# FEU31_Part2.net
KiCad netlist of a schematic drawn in Altium Designer
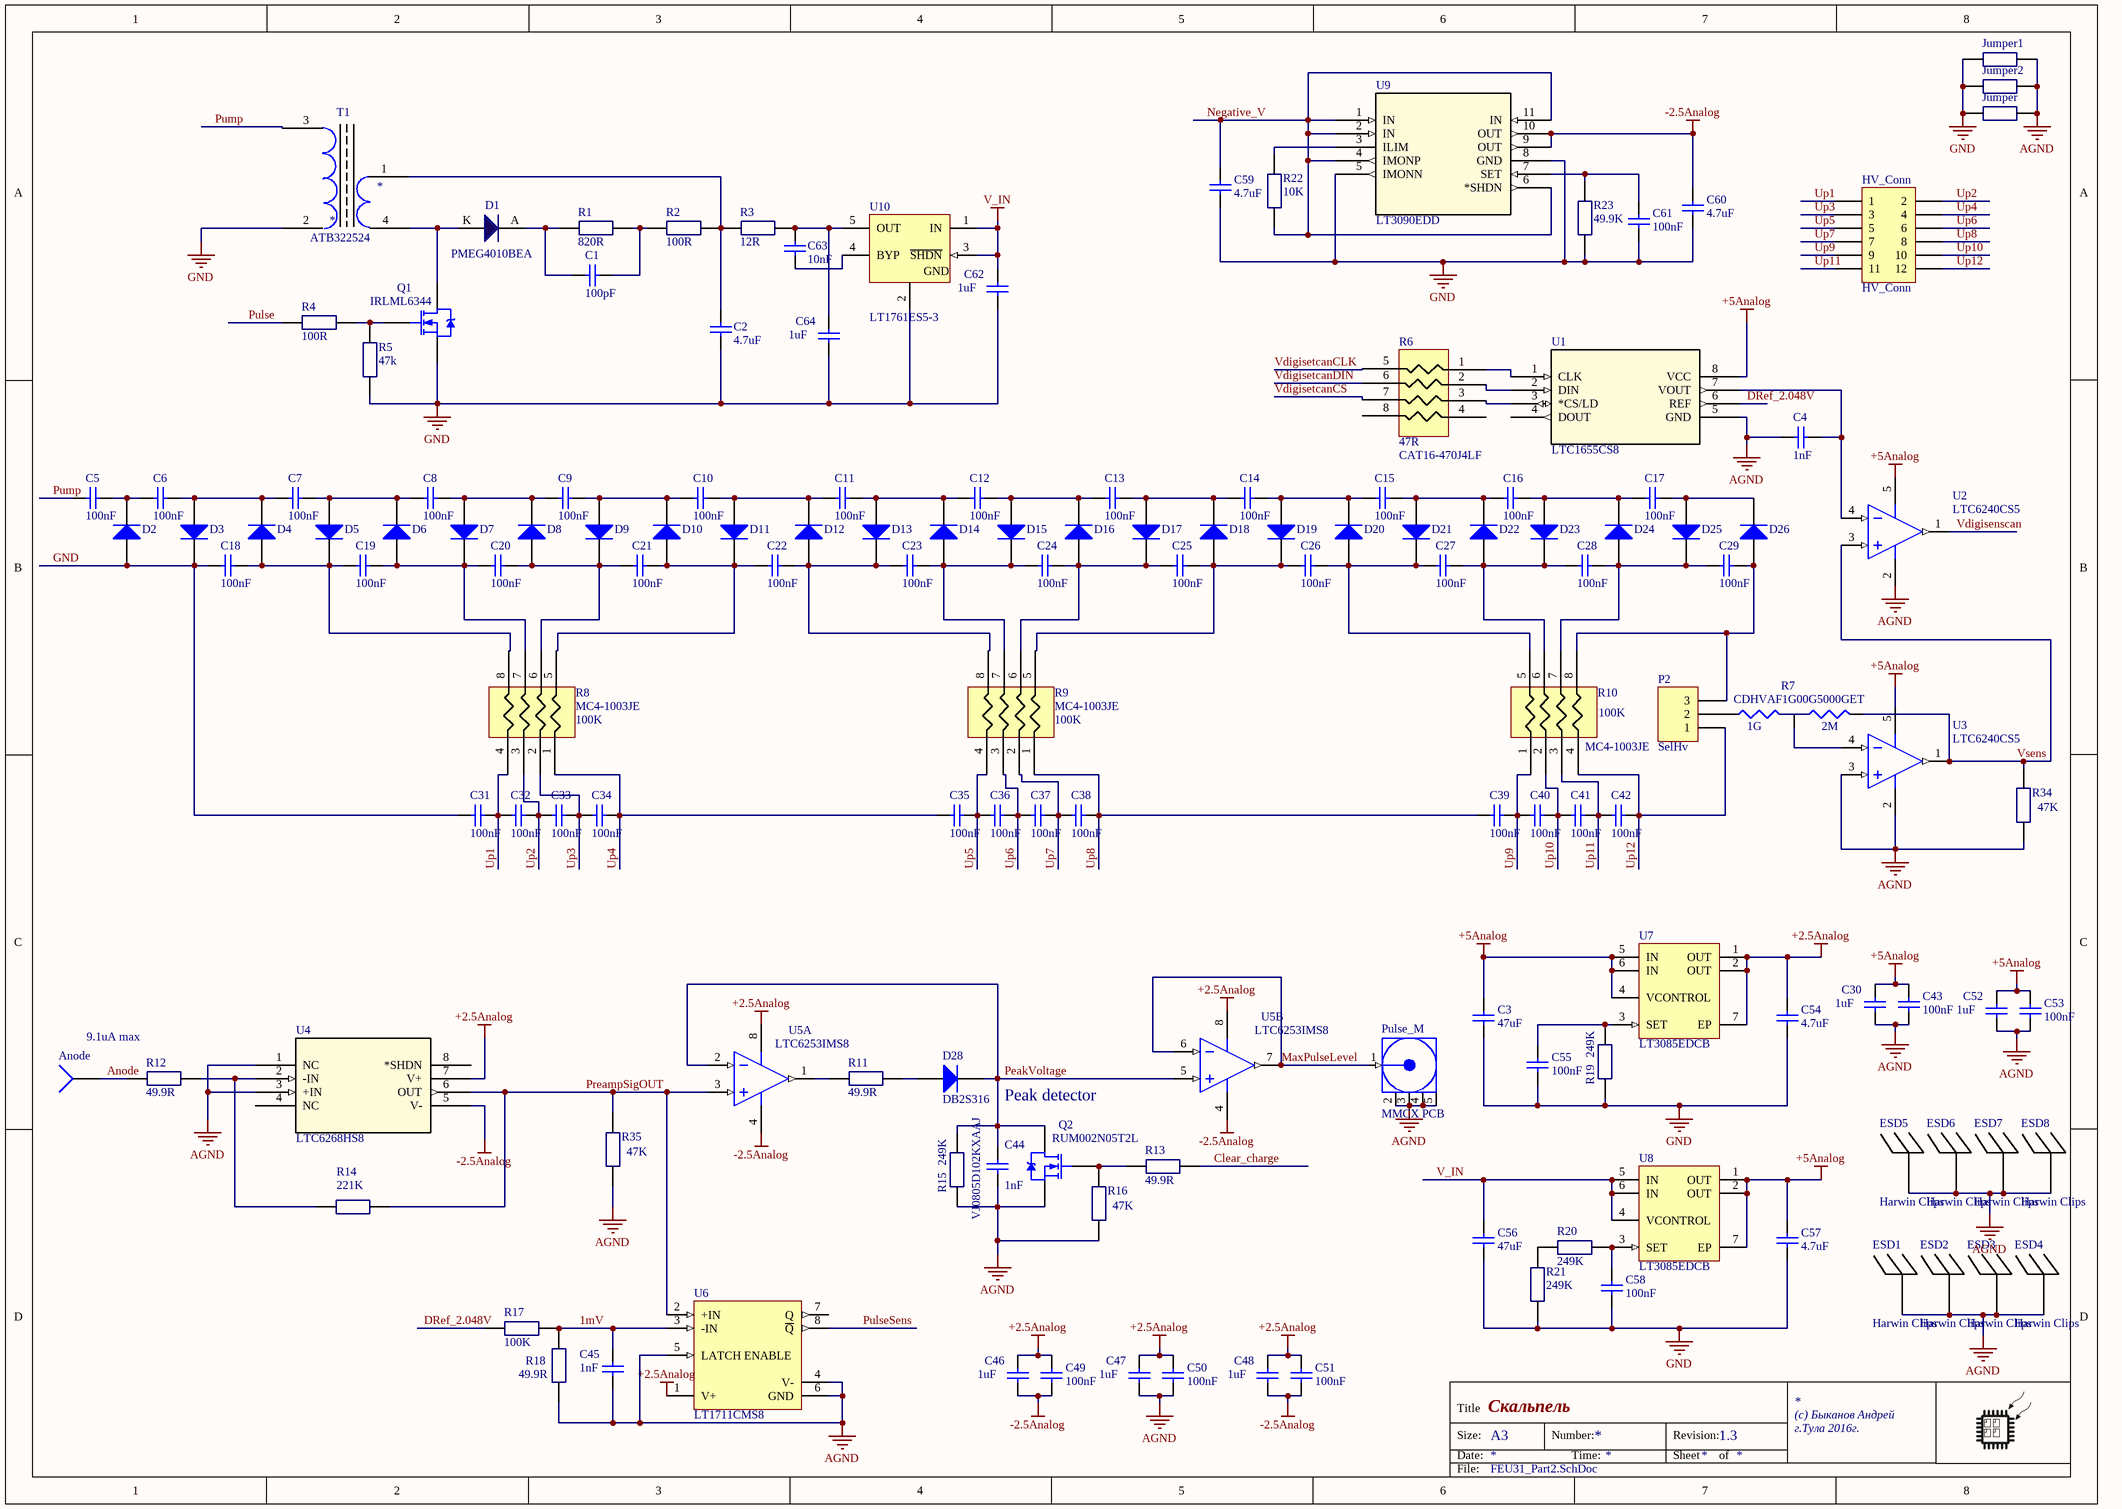
[diagram p0: FEU31_Part2.SchDoc]

(export (version "E")
  (design (tool "Eeschema 10.0.6"))
  (components
    (comp (ref "Anode")
      (value "Anode")
      (footprint "PMTanode")
      (description "Socket")
      (fields (field (name "PUBLISHER") "Altium Limited"))
      (libsource (lib "Miscellaneous Connectors") (part "Socket"))
    )
    (comp (ref "C1")
      (value "100pF")
      (footprint "1608[0603]_CAP")
      (description "Capacitor (Semiconductor SIM Model)")
      (fields (field (name "PUBLISHER") "Altium Limited"))
      (libsource (lib "Miscellaneous Devices") (part "Cap Semi"))
    )
    (comp (ref "C2")
      (value "4.7uF")
      (footprint "Miscellaneous Devices:C1206")
      (description "Capacitor (Semiconductor SIM Model)")
      (fields (field (name "PUBLISHER") "Altium Limited"))
      (libsource (lib "Miscellaneous Devices") (part "Cap Semi"))
    )
    (comp (ref "C3")
      (value "47uF")
      (footprint "C1206")
      (description "Capacitor (Semiconductor SIM Model)")
      (fields (field (name "PUBLISHER") "Altium Limited"))
      (libsource (lib "Miscellaneous Devices") (part "Cap Semi"))
    )
    (comp (ref "C4")
      (value "1nF")
      (footprint "1608[0603]_CAP")
      (description "Capacitor (Semiconductor SIM Model)")
      (fields (field (name "PUBLISHER") "Altium Limited"))
      (libsource (lib "Miscellaneous Devices") (part "Cap Semi"))
    )
    (comp (ref "C5")
      (value "100nF")
      (footprint "Miscellaneous Devices:C1206")
      (description "Capacitor (Semiconductor SIM Model)")
      (fields (field (name "PUBLISHER") "Altium Limited"))
      (libsource (lib "Miscellaneous Devices") (part "Cap Semi"))
    )
    (comp (ref "C6")
      (value "100nF")
      (footprint "Miscellaneous Devices:C1206")
      (description "Capacitor (Semiconductor SIM Model)")
      (fields (field (name "PUBLISHER") "Altium Limited"))
      (libsource (lib "Miscellaneous Devices") (part "Cap Semi"))
    )
    (comp (ref "C7")
      (value "100nF")
      (footprint "Miscellaneous Devices:C1206")
      (description "Capacitor (Semiconductor SIM Model)")
      (fields (field (name "PUBLISHER") "Altium Limited"))
      (libsource (lib "Miscellaneous Devices") (part "Cap Semi"))
    )
    (comp (ref "C8")
      (value "100nF")
      (footprint "Miscellaneous Devices:C1206")
      (description "Capacitor (Semiconductor SIM Model)")
      (fields (field (name "PUBLISHER") "Altium Limited"))
      (libsource (lib "Miscellaneous Devices") (part "Cap Semi"))
    )
    (comp (ref "C9")
      (value "100nF")
      (footprint "Miscellaneous Devices:C1206")
      (description "Capacitor (Semiconductor SIM Model)")
      (fields (field (name "PUBLISHER") "Altium Limited"))
      (libsource (lib "Miscellaneous Devices") (part "Cap Semi"))
    )
    (comp (ref "C10")
      (value "100nF")
      (footprint "Miscellaneous Devices:C1206")
      (description "Capacitor (Semiconductor SIM Model)")
      (fields (field (name "PUBLISHER") "Altium Limited"))
      (libsource (lib "Miscellaneous Devices") (part "Cap Semi"))
    )
    (comp (ref "C11")
      (value "100nF")
      (footprint "Miscellaneous Devices:C1206")
      (description "Capacitor (Semiconductor SIM Model)")
      (fields (field (name "PUBLISHER") "Altium Limited"))
      (libsource (lib "Miscellaneous Devices") (part "Cap Semi"))
    )
    (comp (ref "C12")
      (value "100nF")
      (footprint "Miscellaneous Devices:C1206")
      (description "Capacitor (Semiconductor SIM Model)")
      (fields (field (name "PUBLISHER") "Altium Limited"))
      (libsource (lib "Miscellaneous Devices") (part "Cap Semi"))
    )
    (comp (ref "C13")
      (value "100nF")
      (footprint "Miscellaneous Devices:C1206")
      (description "Capacitor (Semiconductor SIM Model)")
      (fields (field (name "PUBLISHER") "Altium Limited"))
      (libsource (lib "Miscellaneous Devices") (part "Cap Semi"))
    )
    (comp (ref "C14")
      (value "100nF")
      (footprint "Miscellaneous Devices:C1206")
      (description "Capacitor (Semiconductor SIM Model)")
      (fields (field (name "PUBLISHER") "Altium Limited"))
      (libsource (lib "Miscellaneous Devices") (part "Cap Semi"))
    )
    (comp (ref "C15")
      (value "100nF")
      (footprint "Miscellaneous Devices:C1206")
      (description "Capacitor (Semiconductor SIM Model)")
      (fields (field (name "PUBLISHER") "Altium Limited"))
      (libsource (lib "Miscellaneous Devices") (part "Cap Semi"))
    )
    (comp (ref "C16")
      (value "100nF")
      (footprint "Miscellaneous Devices:C1206")
      (description "Capacitor (Semiconductor SIM Model)")
      (fields (field (name "PUBLISHER") "Altium Limited"))
      (libsource (lib "Miscellaneous Devices") (part "Cap Semi"))
    )
    (comp (ref "C17")
      (value "100nF")
      (footprint "Miscellaneous Devices:C1206")
      (description "Capacitor (Semiconductor SIM Model)")
      (fields (field (name "PUBLISHER") "Altium Limited"))
      (libsource (lib "Miscellaneous Devices") (part "Cap Semi"))
    )
    (comp (ref "C18")
      (value "100nF")
      (footprint "Miscellaneous Devices:C1206")
      (description "Capacitor (Semiconductor SIM Model)")
      (fields (field (name "PUBLISHER") "Altium Limited"))
      (libsource (lib "Miscellaneous Devices") (part "Cap Semi"))
    )
    (comp (ref "C19")
      (value "100nF")
      (footprint "Miscellaneous Devices:C1206")
      (description "Capacitor (Semiconductor SIM Model)")
      (fields (field (name "PUBLISHER") "Altium Limited"))
      (libsource (lib "Miscellaneous Devices") (part "Cap Semi"))
    )
    (comp (ref "C20")
      (value "100nF")
      (footprint "Miscellaneous Devices:C1206")
      (description "Capacitor (Semiconductor SIM Model)")
      (fields (field (name "PUBLISHER") "Altium Limited"))
      (libsource (lib "Miscellaneous Devices") (part "Cap Semi"))
    )
    (comp (ref "C21")
      (value "100nF")
      (footprint "Miscellaneous Devices:C1206")
      (description "Capacitor (Semiconductor SIM Model)")
      (fields (field (name "PUBLISHER") "Altium Limited"))
      (libsource (lib "Miscellaneous Devices") (part "Cap Semi"))
    )
    (comp (ref "C22")
      (value "100nF")
      (footprint "Miscellaneous Devices:C1206")
      (description "Capacitor (Semiconductor SIM Model)")
      (fields (field (name "PUBLISHER") "Altium Limited"))
      (libsource (lib "Miscellaneous Devices") (part "Cap Semi"))
    )
    (comp (ref "C23")
      (value "100nF")
      (footprint "Miscellaneous Devices:C1206")
      (description "Capacitor (Semiconductor SIM Model)")
      (fields (field (name "PUBLISHER") "Altium Limited"))
      (libsource (lib "Miscellaneous Devices") (part "Cap Semi"))
    )
    (comp (ref "C24")
      (value "100nF")
      (footprint "Miscellaneous Devices:C1206")
      (description "Capacitor (Semiconductor SIM Model)")
      (fields (field (name "PUBLISHER") "Altium Limited"))
      (libsource (lib "Miscellaneous Devices") (part "Cap Semi"))
    )
    (comp (ref "C25")
      (value "100nF")
      (footprint "Miscellaneous Devices:C1206")
      (description "Capacitor (Semiconductor SIM Model)")
      (fields (field (name "PUBLISHER") "Altium Limited"))
      (libsource (lib "Miscellaneous Devices") (part "Cap Semi"))
    )
    (comp (ref "C26")
      (value "100nF")
      (footprint "Miscellaneous Devices:C1206")
      (description "Capacitor (Semiconductor SIM Model)")
      (fields (field (name "PUBLISHER") "Altium Limited"))
      (libsource (lib "Miscellaneous Devices") (part "Cap Semi"))
    )
    (comp (ref "C27")
      (value "100nF")
      (footprint "Miscellaneous Devices:C1206")
      (description "Capacitor (Semiconductor SIM Model)")
      (fields (field (name "PUBLISHER") "Altium Limited"))
      (libsource (lib "Miscellaneous Devices") (part "Cap Semi"))
    )
    (comp (ref "C28")
      (value "100nF")
      (footprint "Miscellaneous Devices:C1206")
      (description "Capacitor (Semiconductor SIM Model)")
      (fields (field (name "PUBLISHER") "Altium Limited"))
      (libsource (lib "Miscellaneous Devices") (part "Cap Semi"))
    )
    (comp (ref "C29")
      (value "100nF")
      (footprint "Miscellaneous Devices:C1206")
      (description "Capacitor (Semiconductor SIM Model)")
      (fields (field (name "PUBLISHER") "Altium Limited"))
      (libsource (lib "Miscellaneous Devices") (part "Cap Semi"))
    )
    (comp (ref "C30")
      (value "1uF")
      (footprint "1608[0603]_CAP")
      (description "Capacitor (Semiconductor SIM Model)")
      (fields (field (name "PUBLISHER") "Altium Limited"))
      (libsource (lib "Miscellaneous Devices") (part "Cap Semi"))
    )
    (comp (ref "C31")
      (value "100nF")
      (footprint "Miscellaneous Devices:C1206")
      (description "Capacitor (Semiconductor SIM Model)")
      (fields (field (name "PUBLISHER") "Altium Limited"))
      (libsource (lib "Miscellaneous Devices") (part "Cap Semi"))
    )
    (comp (ref "C32")
      (value "100nF")
      (footprint "Miscellaneous Devices:C1206")
      (description "Capacitor (Semiconductor SIM Model)")
      (fields (field (name "PUBLISHER") "Altium Limited"))
      (libsource (lib "Miscellaneous Devices") (part "Cap Semi"))
    )
    (comp (ref "C33")
      (value "100nF")
      (footprint "Miscellaneous Devices:C1206")
      (description "Capacitor (Semiconductor SIM Model)")
      (fields (field (name "PUBLISHER") "Altium Limited"))
      (libsource (lib "Miscellaneous Devices") (part "Cap Semi"))
    )
    (comp (ref "C34")
      (value "100nF")
      (footprint "Miscellaneous Devices:C1206")
      (description "Capacitor (Semiconductor SIM Model)")
      (fields (field (name "PUBLISHER") "Altium Limited"))
      (libsource (lib "Miscellaneous Devices") (part "Cap Semi"))
    )
    (comp (ref "C35")
      (value "100nF")
      (footprint "Miscellaneous Devices:C1206")
      (description "Capacitor (Semiconductor SIM Model)")
      (fields (field (name "PUBLISHER") "Altium Limited"))
      (libsource (lib "Miscellaneous Devices") (part "Cap Semi"))
    )
    (comp (ref "C36")
      (value "100nF")
      (footprint "Miscellaneous Devices:C1206")
      (description "Capacitor (Semiconductor SIM Model)")
      (fields (field (name "PUBLISHER") "Altium Limited"))
      (libsource (lib "Miscellaneous Devices") (part "Cap Semi"))
    )
    (comp (ref "C37")
      (value "100nF")
      (footprint "Miscellaneous Devices:C1206")
      (description "Capacitor (Semiconductor SIM Model)")
      (fields (field (name "PUBLISHER") "Altium Limited"))
      (libsource (lib "Miscellaneous Devices") (part "Cap Semi"))
    )
    (comp (ref "C38")
      (value "100nF")
      (footprint "Miscellaneous Devices:C1206")
      (description "Capacitor (Semiconductor SIM Model)")
      (fields (field (name "PUBLISHER") "Altium Limited"))
      (libsource (lib "Miscellaneous Devices") (part "Cap Semi"))
    )
    (comp (ref "C39")
      (value "100nF")
      (footprint "Miscellaneous Devices:C1206")
      (description "Capacitor (Semiconductor SIM Model)")
      (fields (field (name "PUBLISHER") "Altium Limited"))
      (libsource (lib "Miscellaneous Devices") (part "Cap Semi"))
    )
    (comp (ref "C40")
      (value "100nF")
      (footprint "Miscellaneous Devices:C1206")
      (description "Capacitor (Semiconductor SIM Model)")
      (fields (field (name "PUBLISHER") "Altium Limited"))
      (libsource (lib "Miscellaneous Devices") (part "Cap Semi"))
    )
    (comp (ref "C41")
      (value "100nF")
      (footprint "Miscellaneous Devices:C1206")
      (description "Capacitor (Semiconductor SIM Model)")
      (fields (field (name "PUBLISHER") "Altium Limited"))
      (libsource (lib "Miscellaneous Devices") (part "Cap Semi"))
    )
    (comp (ref "C42")
      (value "100nF")
      (footprint "Miscellaneous Devices:C1206")
      (description "Capacitor (Semiconductor SIM Model)")
      (fields (field (name "PUBLISHER") "Altium Limited"))
      (libsource (lib "Miscellaneous Devices") (part "Cap Semi"))
    )
    (comp (ref "C43")
      (value "100nF")
      (footprint "1608[0603]_CAP")
      (description "Capacitor (Semiconductor SIM Model)")
      (fields (field (name "PUBLISHER") "Altium Limited"))
      (libsource (lib "Miscellaneous Devices") (part "Cap Semi"))
    )
    (comp (ref "C44")
      (value "1nF")
      (footprint "0805_CAP")
      (description "Capacitor (Semiconductor SIM Model)")
      (fields (field (name "ORDER") "VJ0805D102KXAAJ") (field (name "PUBLISHER") "Altium Limited"))
      (libsource (lib "Miscellaneous Devices") (part "Cap Semi"))
    )
    (comp (ref "C45")
      (value "1nF")
      (footprint "1608[0603]_CAP")
      (description "Capacitor (Semiconductor SIM Model)")
      (fields (field (name "PUBLISHER") "Altium Limited"))
      (libsource (lib "Miscellaneous Devices") (part "Cap Semi"))
    )
    (comp (ref "C46")
      (value "1uF")
      (footprint "1608[0603]_CAP")
      (description "Capacitor (Semiconductor SIM Model)")
      (fields (field (name "PUBLISHER") "Altium Limited"))
      (libsource (lib "Miscellaneous Devices") (part "Cap Semi"))
    )
    (comp (ref "C47")
      (value "1uF")
      (footprint "1608[0603]_CAP")
      (description "Capacitor (Semiconductor SIM Model)")
      (fields (field (name "PUBLISHER") "Altium Limited"))
      (libsource (lib "Miscellaneous Devices") (part "Cap Semi"))
    )
    (comp (ref "C48")
      (value "1uF")
      (footprint "1608[0603]_CAP")
      (description "Capacitor (Semiconductor SIM Model)")
      (fields (field (name "PUBLISHER") "Altium Limited"))
      (libsource (lib "Miscellaneous Devices") (part "Cap Semi"))
    )
    (comp (ref "C49")
      (value "100nF")
      (footprint "1608[0603]_CAP")
      (description "Capacitor (Semiconductor SIM Model)")
      (fields (field (name "PUBLISHER") "Altium Limited"))
      (libsource (lib "Miscellaneous Devices") (part "Cap Semi"))
    )
    (comp (ref "C50")
      (value "100nF")
      (footprint "1608[0603]_CAP")
      (description "Capacitor (Semiconductor SIM Model)")
      (fields (field (name "PUBLISHER") "Altium Limited"))
      (libsource (lib "Miscellaneous Devices") (part "Cap Semi"))
    )
    (comp (ref "C51")
      (value "100nF")
      (footprint "1608[0603]_CAP")
      (description "Capacitor (Semiconductor SIM Model)")
      (fields (field (name "PUBLISHER") "Altium Limited"))
      (libsource (lib "Miscellaneous Devices") (part "Cap Semi"))
    )
    (comp (ref "C52")
      (value "1uF")
      (footprint "1608[0603]_CAP")
      (description "Capacitor (Semiconductor SIM Model)")
      (fields (field (name "PUBLISHER") "Altium Limited"))
      (libsource (lib "Miscellaneous Devices") (part "Cap Semi"))
    )
    (comp (ref "C53")
      (value "100nF")
      (footprint "1608[0603]_CAP")
      (description "Capacitor (Semiconductor SIM Model)")
      (fields (field (name "PUBLISHER") "Altium Limited"))
      (libsource (lib "Miscellaneous Devices") (part "Cap Semi"))
    )
    (comp (ref "C54")
      (value "4.7uF")
      (footprint "C1206")
      (description "Capacitor (Semiconductor SIM Model)")
      (fields (field (name "PUBLISHER") "Altium Limited"))
      (libsource (lib "Miscellaneous Devices") (part "Cap Semi"))
    )
    (comp (ref "C55")
      (value "100nF")
      (footprint "1608[0603]_CAP")
      (description "Capacitor (Semiconductor SIM Model)")
      (fields (field (name "PUBLISHER") "Altium Limited"))
      (libsource (lib "Miscellaneous Devices") (part "Cap Semi"))
    )
    (comp (ref "C56")
      (value "47uF")
      (footprint "C1206")
      (description "Capacitor (Semiconductor SIM Model)")
      (fields (field (name "PUBLISHER") "Altium Limited"))
      (libsource (lib "Miscellaneous Devices") (part "Cap Semi"))
    )
    (comp (ref "C57")
      (value "4.7uF")
      (footprint "C1206")
      (description "Capacitor (Semiconductor SIM Model)")
      (fields (field (name "PUBLISHER") "Altium Limited"))
      (libsource (lib "Miscellaneous Devices") (part "Cap Semi"))
    )
    (comp (ref "C58")
      (value "100nF")
      (footprint "1608[0603]_CAP")
      (description "Capacitor (Semiconductor SIM Model)")
      (fields (field (name "PUBLISHER") "Altium Limited"))
      (libsource (lib "Miscellaneous Devices") (part "Cap Semi"))
    )
    (comp (ref "C59")
      (value "4.7uF")
      (footprint "C1206")
      (description "Capacitor (Semiconductor SIM Model)")
      (fields (field (name "PUBLISHER") "Altium Limited"))
      (libsource (lib "Miscellaneous Devices") (part "Cap Semi"))
    )
    (comp (ref "C60")
      (value "4.7uF")
      (footprint "C1206")
      (description "Capacitor (Semiconductor SIM Model)")
      (fields (field (name "PUBLISHER") "Altium Limited"))
      (libsource (lib "Miscellaneous Devices") (part "Cap Semi"))
    )
    (comp (ref "C61")
      (value "100nF")
      (footprint "1608[0603]_CAP")
      (description "Capacitor (Semiconductor SIM Model)")
      (fields (field (name "PUBLISHER") "Altium Limited"))
      (libsource (lib "Miscellaneous Devices") (part "Cap Semi"))
    )
    (comp (ref "C62")
      (value "1uF")
      (footprint "1608[0603]_CAP")
      (description "Capacitor (Semiconductor SIM Model)")
      (fields (field (name "PUBLISHER") "Altium Limited"))
      (libsource (lib "Miscellaneous Devices") (part "Cap Semi"))
    )
    (comp (ref "C63")
      (value "10nF")
      (footprint "1608[0603]_CAP")
      (description "Capacitor (Semiconductor SIM Model)")
      (fields (field (name "PUBLISHER") "Altium Limited"))
      (libsource (lib "Miscellaneous Devices") (part "Cap Semi"))
    )
    (comp (ref "C64")
      (value "1uF")
      (footprint "1608[0603]_CAP")
      (description "Capacitor (Semiconductor SIM Model)")
      (fields (field (name "PUBLISHER") "Altium Limited"))
      (libsource (lib "Miscellaneous Devices") (part "Cap Semi"))
    )
    (comp (ref "D1")
      (value "PMEG4010BEA")
      (footprint "PMEG4010BEA")
      (libsource (lib "My SCH library") (part "PMEG4010BEA"))
    )
    (comp (ref "D2")
      (value "~")
      (footprint "DA2JF8100L")
      (description "Default Diode")
      (fields (field (name "PUBLISHER") "Altium Limited"))
      (libsource (lib "Miscellaneous Devices") (part "Diode"))
    )
    (comp (ref "D3")
      (value "~")
      (footprint "DA2JF8100L")
      (description "Default Diode")
      (fields (field (name "PUBLISHER") "Altium Limited"))
      (libsource (lib "Miscellaneous Devices") (part "Diode"))
    )
    (comp (ref "D4")
      (value "~")
      (footprint "DA2JF8100L")
      (description "Default Diode")
      (fields (field (name "PUBLISHER") "Altium Limited"))
      (libsource (lib "Miscellaneous Devices") (part "Diode"))
    )
    (comp (ref "D5")
      (value "~")
      (footprint "DA2JF8100L")
      (description "Default Diode")
      (fields (field (name "PUBLISHER") "Altium Limited"))
      (libsource (lib "Miscellaneous Devices") (part "Diode"))
    )
    (comp (ref "D6")
      (value "~")
      (footprint "DA2JF8100L")
      (description "Default Diode")
      (fields (field (name "PUBLISHER") "Altium Limited"))
      (libsource (lib "Miscellaneous Devices") (part "Diode"))
    )
    (comp (ref "D7")
      (value "~")
      (footprint "DA2JF8100L")
      (description "Default Diode")
      (fields (field (name "PUBLISHER") "Altium Limited"))
      (libsource (lib "Miscellaneous Devices") (part "Diode"))
    )
    (comp (ref "D8")
      (value "~")
      (footprint "DA2JF8100L")
      (description "Default Diode")
      (fields (field (name "PUBLISHER") "Altium Limited"))
      (libsource (lib "Miscellaneous Devices") (part "Diode"))
    )
    (comp (ref "D9")
      (value "~")
      (footprint "DA2JF8100L")
      (description "Default Diode")
      (fields (field (name "PUBLISHER") "Altium Limited"))
      (libsource (lib "Miscellaneous Devices") (part "Diode"))
    )
    (comp (ref "D10")
      (value "~")
      (footprint "DA2JF8100L")
      (description "Default Diode")
      (fields (field (name "PUBLISHER") "Altium Limited"))
      (libsource (lib "Miscellaneous Devices") (part "Diode"))
    )
    (comp (ref "D11")
      (value "~")
      (footprint "DA2JF8100L")
      (description "Default Diode")
      (fields (field (name "PUBLISHER") "Altium Limited"))
      (libsource (lib "Miscellaneous Devices") (part "Diode"))
    )
    (comp (ref "D12")
      (value "~")
      (footprint "DA2JF8100L")
      (description "Default Diode")
      (fields (field (name "PUBLISHER") "Altium Limited"))
      (libsource (lib "Miscellaneous Devices") (part "Diode"))
    )
    (comp (ref "D13")
      (value "~")
      (footprint "DA2JF8100L")
      (description "Default Diode")
      (fields (field (name "PUBLISHER") "Altium Limited"))
      (libsource (lib "Miscellaneous Devices") (part "Diode"))
    )
    (comp (ref "D14")
      (value "~")
      (footprint "DA2JF8100L")
      (description "Default Diode")
      (fields (field (name "PUBLISHER") "Altium Limited"))
      (libsource (lib "Miscellaneous Devices") (part "Diode"))
    )
    (comp (ref "D15")
      (value "~")
      (footprint "DA2JF8100L")
      (description "Default Diode")
      (fields (field (name "PUBLISHER") "Altium Limited"))
      (libsource (lib "Miscellaneous Devices") (part "Diode"))
    )
    (comp (ref "D16")
      (value "~")
      (footprint "DA2JF8100L")
      (description "Default Diode")
      (fields (field (name "PUBLISHER") "Altium Limited"))
      (libsource (lib "Miscellaneous Devices") (part "Diode"))
    )
    (comp (ref "D17")
      (value "~")
      (footprint "DA2JF8100L")
      (description "Default Diode")
      (fields (field (name "PUBLISHER") "Altium Limited"))
      (libsource (lib "Miscellaneous Devices") (part "Diode"))
    )
    (comp (ref "D18")
      (value "~")
      (footprint "DA2JF8100L")
      (description "Default Diode")
      (fields (field (name "PUBLISHER") "Altium Limited"))
      (libsource (lib "Miscellaneous Devices") (part "Diode"))
    )
    (comp (ref "D19")
      (value "~")
      (footprint "DA2JF8100L")
      (description "Default Diode")
      (fields (field (name "PUBLISHER") "Altium Limited"))
      (libsource (lib "Miscellaneous Devices") (part "Diode"))
    )
    (comp (ref "D20")
      (value "~")
      (footprint "DA2JF8100L")
      (description "Default Diode")
      (fields (field (name "PUBLISHER") "Altium Limited"))
      (libsource (lib "Miscellaneous Devices") (part "Diode"))
    )
    (comp (ref "D21")
      (value "~")
      (footprint "DA2JF8100L")
      (description "Default Diode")
      (fields (field (name "PUBLISHER") "Altium Limited"))
      (libsource (lib "Miscellaneous Devices") (part "Diode"))
    )
    (comp (ref "D22")
      (value "~")
      (footprint "DA2JF8100L")
      (description "Default Diode")
      (fields (field (name "PUBLISHER") "Altium Limited"))
      (libsource (lib "Miscellaneous Devices") (part "Diode"))
    )
    (comp (ref "D23")
      (value "~")
      (footprint "DA2JF8100L")
      (description "Default Diode")
      (fields (field (name "PUBLISHER") "Altium Limited"))
      (libsource (lib "Miscellaneous Devices") (part "Diode"))
    )
    (comp (ref "D24")
      (value "~")
      (footprint "DA2JF8100L")
      (description "Default Diode")
      (fields (field (name "PUBLISHER") "Altium Limited"))
      (libsource (lib "Miscellaneous Devices") (part "Diode"))
    )
    (comp (ref "D25")
      (value "~")
      (footprint "DA2JF8100L")
      (description "Default Diode")
      (fields (field (name "PUBLISHER") "Altium Limited"))
      (libsource (lib "Miscellaneous Devices") (part "Diode"))
    )
    (comp (ref "D26")
      (value "~")
      (footprint "DA2JF8100L")
      (description "Default Diode")
      (fields (field (name "PUBLISHER") "Altium Limited"))
      (libsource (lib "Miscellaneous Devices") (part "Diode"))
    )
    (comp (ref "D28")
      (value "DB2S316")
      (footprint "SSMini2-F5-B")
      (description "Default Diode")
      (fields (field (name "PUBLISHER") "Altium Limited"))
      (libsource (lib "Miscellaneous Devices") (part "Diode"))
    )
    (comp (ref "ESD1")
      (value "Harwin Clips")
      (footprint "HARWIN - S0981-46R - CLIP")
      (libsource (lib "My SCH library") (part "Harwin Clips"))
    )
    (comp (ref "ESD2")
      (value "Harwin Clips")
      (footprint "HARWIN - S0981-46R - CLIP")
      (libsource (lib "My SCH library") (part "Harwin Clips"))
    )
    (comp (ref "ESD3")
      (value "Harwin Clips")
      (footprint "HARWIN - S0981-46R - CLIP")
      (libsource (lib "My SCH library") (part "Harwin Clips"))
    )
    (comp (ref "ESD4")
      (value "Harwin Clips")
      (footprint "HARWIN - S0981-46R - CLIP")
      (libsource (lib "My SCH library") (part "Harwin Clips"))
    )
    (comp (ref "ESD5")
      (value "Harwin Clips")
      (footprint "HARWIN - S0981-46R - CLIP")
      (libsource (lib "My SCH library") (part "Harwin Clips"))
    )
    (comp (ref "ESD6")
      (value "Harwin Clips")
      (footprint "HARWIN - S0981-46R - CLIP")
      (libsource (lib "My SCH library") (part "Harwin Clips"))
    )
    (comp (ref "ESD7")
      (value "Harwin Clips")
      (footprint "HARWIN - S0981-46R - CLIP")
      (libsource (lib "My SCH library") (part "Harwin Clips"))
    )
    (comp (ref "ESD8")
      (value "Harwin Clips")
      (footprint "HARWIN - S0981-46R - CLIP")
      (libsource (lib "My SCH library") (part "Harwin Clips"))
    )
    (comp (ref "HV_Conn")
      (value "HV_Conn")
      (footprint "HDR2X6H")
      (description "Header, 6-Pin, Dual row, Right Angle")
      (fields (field (name "PUBLISHER") "Altium Limited"))
      (libsource (lib "Miscellaneous Connectors") (part "Header 6X2H"))
    )
    (comp (ref "Jumper")
      (value "~")
      (footprint "0402 jumper")
      (libsource (lib "Микрон-3") (part "Resistor 0805"))
    )
    (comp (ref "Jumper1")
      (value "~")
      (footprint "0402 jumper")
      (libsource (lib "Микрон-3") (part "Resistor 0805"))
    )
    (comp (ref "Jumper2")
      (value "~")
      (footprint "0402 jumper")
      (libsource (lib "Микрон-3") (part "Resistor 0805"))
    )
    (comp (ref "P2")
      (value "SelHv")
      (footprint "HDR1X3")
      (description "Header, 3-Pin")
      (fields (field (name "PUBLISHER") "Altium Limited"))
      (libsource (lib "Miscellaneous Connectors") (part "Header 3"))
    )
    (comp (ref "Pulse_M")
      (value "MMCX PCB")
      (footprint "MMCX2.54-V5")
      (description "RF Coaxial PCB Connector, MMCX; Thru-Hole, Vertical Mount Plug,  50 Ohm Impedance")
      (fields (field (name "PUBLISHER") "Altium Limited"))
      (libsource (lib "Miscellaneous Connectors") (part "COAX-M"))
    )
    (comp (ref "Q1")
      (value "IRLML6344")
      (footprint "SOT-23_N")
      (description "HEXFET Power MOSFET")
      (fields (field (name "PUBLISHER") "Altium Limited"))
      (libsource (lib "IR Discrete MOSFET - Power") (part "IRLML2402"))
    )
    (comp (ref "Q2")
      (value "RUM002N05T2L")
      (footprint "RUM002N05")
      (description "HEXFET Power MOSFET")
      (fields (field (name "PUBLISHER") "Altium Limited"))
      (libsource (lib "IR Discrete MOSFET - Power") (part "IRLML2402"))
    )
    (comp (ref "R1")
      (value "820R")
      (footprint "1608[0603]_RES")
      (libsource (lib "Микрон-3") (part "Resistor 0805"))
    )
    (comp (ref "R2")
      (value "100R")
      (footprint "1608[0603]_RES")
      (libsource (lib "Микрон-3") (part "Resistor 0805"))
    )
    (comp (ref "R3")
      (value "12R")
      (footprint "1608[0603]_RES")
      (libsource (lib "Микрон-3") (part "Resistor 0805"))
    )
    (comp (ref "R4")
      (value "100R")
      (footprint "1608[0603]_RES")
      (libsource (lib "Микрон-3") (part "Resistor 0805"))
    )
    (comp (ref "R5")
      (value "47k")
      (footprint "1608[0603]_RES")
      (libsource (lib "Микрон-3") (part "Resistor 0805"))
    )
    (comp (ref "R6")
      (value "47R")
      (footprint "CAT16-470J4LF")
      (fields (field (name "ORDER") "CAT16-470J4LF"))
      (libsource (lib "") (part "CAT16-470J4LF_2"))
    )
    (comp (ref "R7")
      (value "1G")
      (footprint "CDHV2512")
      (fields
        (field (name "VALUE2") "2M")
        (field (name "ORDER") "CDHVAF1G00G5000GET")
        (field (name "Comment") "CDHVAF1G00G5000GET")
        (field (name "PUBLISHER") "Altium Limited")
      )
      (libsource (lib "My SCH library") (part "CDHVAF1G00G5000GET"))
    )
    (comp (ref "R8")
      (value "MC4-1003JE")
      (footprint "MC4")
      (fields (field (name "ALTIUM_VALUE") "100K"))
      (libsource (lib "") (part "CAT16-470J4LF_1"))
    )
    (comp (ref "R9")
      (value "MC4-1003JE")
      (footprint "MC4")
      (fields (field (name "ALTIUM_VALUE") "100K"))
      (libsource (lib "") (part "CAT16-470J4LF_1"))
    )
    (comp (ref "R10")
      (value "MC4-1003JE")
      (footprint "MC4")
      (fields (field (name "ALTIUM_VALUE") "100K"))
      (libsource (lib "My SCH library") (part "CAT16-470J4LF"))
    )
    (comp (ref "R11")
      (value "49.9R")
      (footprint "1608[0603]_RES")
      (libsource (lib "Микрон-3") (part "Resistor 0805"))
    )
    (comp (ref "R12")
      (value "49.9R")
      (footprint "1608[0603]_RES")
      (libsource (lib "Микрон-3") (part "Resistor 0805"))
    )
    (comp (ref "R13")
      (value "49.9R")
      (footprint "1608[0603]_RES")
      (libsource (lib "Микрон-3") (part "Resistor 0805"))
    )
    (comp (ref "R14")
      (value "221K")
      (footprint "1608[0603]_RES")
      (libsource (lib "Микрон-3") (part "Resistor 0805"))
    )
    (comp (ref "R15")
      (value "249K")
      (footprint "1608[0603]_RES")
      (libsource (lib "Микрон-3") (part "Resistor 0805"))
    )
    (comp (ref "R16")
      (value "47K")
      (footprint "1608[0603]_RES")
      (libsource (lib "Микрон-3") (part "Resistor 0805"))
    )
    (comp (ref "R17")
      (value "100K")
      (footprint "1608[0603]_RES")
      (libsource (lib "Микрон-3") (part "Resistor 0805"))
    )
    (comp (ref "R18")
      (value "49.9R")
      (footprint "1608[0603]_RES")
      (libsource (lib "Микрон-3") (part "Resistor 0805"))
    )
    (comp (ref "R19")
      (value "249K")
      (footprint "1608[0603]_RES")
      (libsource (lib "Микрон-3") (part "Resistor 0805"))
    )
    (comp (ref "R20")
      (value "249K")
      (footprint "1608[0603]_RES")
      (libsource (lib "Микрон-3") (part "Resistor 0805"))
    )
    (comp (ref "R21")
      (value "249K")
      (footprint "1608[0603]_RES")
      (libsource (lib "Микрон-3") (part "Resistor 0805"))
    )
    (comp (ref "R22")
      (value "10K")
      (footprint "1608[0603]_RES")
      (libsource (lib "Микрон-3") (part "Resistor 0805"))
    )
    (comp (ref "R23")
      (value "49.9K")
      (footprint "1608[0603]_RES")
      (libsource (lib "Микрон-3") (part "Resistor 0805"))
    )
    (comp (ref "R34")
      (value "47K")
      (footprint "1608[0603]_RES")
      (libsource (lib "Микрон-3") (part "Resistor 0805"))
    )
    (comp (ref "R35")
      (value "47K")
      (footprint "1608[0603]_RES")
      (libsource (lib "Микрон-3") (part "Resistor 0805"))
    )
    (comp (ref "T1")
      (value "ATB322524")
      (footprint "ATB322515-0110")
      (libsource (lib "My SCH library") (part "ATB322515-0110"))
    )
    (comp (ref "U1")
      (value "LTC1655CS8")
      (footprint "SO-8_S")
      (description "Imported")
      (fields (field (name "MANUFACTURER_PART_NUMBER") "ltc1655cs8"))
      (libsource (lib "2017-08-04_11-27-58") (part "LTC1655CS8"))
    )
    (comp (ref "U2")
      (value "LTC6240CS5")
      (footprint "LT-S5-5-TSOT-23_N")
      (fields
        (field (name "LINEAR TECHNOLOGY PART NUMBER") "LTC6240")
        (field (name "MANUFACTURER") "Linear Technology")
        (field (name "PARTNUMBER") "LTC6240CS5#PBF")
      )
      (libsource (lib "Linear Technology Operational Amplifiers (LT2000-LT6000)") (part "LTC6240CS5#PBF"))
    )
    (comp (ref "U3")
      (value "LTC6240CS5")
      (footprint "LT-S5-5-TSOT-23_N")
      (fields
        (field (name "LINEAR TECHNOLOGY PART NUMBER") "LTC6240")
        (field (name "MANUFACTURER") "Linear Technology")
        (field (name "PARTNUMBER") "LTC6240CS5#PBF")
      )
      (libsource (lib "Linear Technology Operational Amplifiers (LT2000-LT6000)") (part "LTC6240CS5#PBF"))
    )
    (comp (ref "U4")
      (value "LTC6268HS8")
      (footprint "SO-8_S")
      (description "Imported")
      (fields (field (name "MANUFACTURER_PART_NUMBER") "ltc6268hs8#pbf"))
      (libsource (lib "2017-08-04_13-53-15") (part "LTC6268HS8PBF"))
    )
    (comp (ref "U5")
      (value "LTC6253IMS8")
      (footprint "LT-MS8-8_N")
      (fields
        (field (name "LINEAR TECHNOLOGY PART NUMBER") "LTC6253")
        (field (name "MANUFACTURER") "Linear Technology")
        (field (name "PARTNUMBER") "LTC6253IMS8#PBF")
      )
      (libsource (lib "Linear Technology Operational Amplifiers (LT2000-LT6000)") (part "LTC6253IMS8#PBF"))
    )
    (comp (ref "U6")
      (value "LT1711CMS8")
      (footprint "LT-MS8_N")
      (fields (field (name "GENERIC PART NUMBER") "LT1711") (field (name "MANUFACTURER") "Linear Technology"))
      (libsource (lib "Linear Technology Comparators") (part "LT1711CMS8"))
    )
    (comp (ref "U7")
      (value "LT3085EDCB")
      (footprint "LT-DCB-6_V")
      (fields (field (name "MANUFACTURER") "Linear Technology") (field (name "PARTNUMBER") "LT3085EDCB#PBF"))
      (libsource (lib "Linear Technology Power Management Current Sources") (part "LT3085EDCB#PBF"))
    )
    (comp (ref "U8")
      (value "LT3085EDCB")
      (footprint "LT-DCB-6_V")
      (fields (field (name "MANUFACTURER") "Linear Technology") (field (name "PARTNUMBER") "LT3085EDCB#PBF"))
      (libsource (lib "Linear Technology Power Management Current Sources") (part "LT3085EDCB#PBF"))
    )
    (comp (ref "U9")
      (value "LT3090EDD")
      (footprint "DFN-10_DD")
      (description "Imported")
      (fields (field (name "MANUFACTURER_PART_NUMBER") "lt3090edd#pbf"))
      (libsource (lib "2017-08-07_08-21-16") (part "LT3090EDDPBF"))
    )
    (comp (ref "U10")
      (value "LT1761ES5-3")
      (footprint "LT-S5-5-TSOT-23_N")
      (fields (field (name "MANUFACTURER") "Linear Technology"))
      (libsource (lib "Linear Technology Power Management LDO Linear Regulators") (part "LT1761ES5-3"))
    )
  )
  (nets
    (net (code "1") (name "+2.5Analog") (class "Default")
      (node (ref "C46") (pin "1") (pinfunction "1_1") (pintype "passive"))
      (node (ref "C47") (pin "1") (pinfunction "1_1") (pintype "passive"))
      (node (ref "C48") (pin "1") (pinfunction "1_1") (pintype "passive"))
      (node (ref "C49") (pin "1") (pinfunction "1_1") (pintype "passive"))
      (node (ref "C50") (pin "1") (pinfunction "1_1") (pintype "passive"))
      (node (ref "C51") (pin "1") (pinfunction "1_1") (pintype "passive"))
      (node (ref "C54") (pin "1") (pinfunction "1_1") (pintype "passive"))
      (node (ref "U4") (pin "7") (pinfunction "V+_7") (pintype "power_in"))
      (node (ref "U5") (pin "8") (pinfunction "V+_8") (pintype "power_in"))
      (node (ref "U6") (pin "1") (pinfunction "V+_1") (pintype "power_in"))
      (node (ref "U7") (pin "1") (pinfunction "OUT_1") (pintype "power_in"))
      (node (ref "U7") (pin "2") (pinfunction "OUT_2") (pintype "power_in"))
      (node (ref "U7") (pin "7") (pinfunction "EP_7") (pintype "power_in"))
    )
    (net (code "2") (name "+5Analog") (class "Default")
      (node (ref "C3") (pin "1") (pinfunction "1_1") (pintype "passive"))
      (node (ref "C30") (pin "1") (pinfunction "1_1") (pintype "passive"))
      (node (ref "C43") (pin "1") (pinfunction "1_1") (pintype "passive"))
      (node (ref "C52") (pin "1") (pinfunction "1_1") (pintype "passive"))
      (node (ref "C53") (pin "1") (pinfunction "1_1") (pintype "passive"))
      (node (ref "C57") (pin "1") (pinfunction "1_1") (pintype "passive"))
      (node (ref "U1") (pin "8") (pinfunction "VCC_8") (pintype "power_in"))
      (node (ref "U2") (pin "5") (pinfunction "V+_5") (pintype "power_in"))
      (node (ref "U3") (pin "5") (pinfunction "V+_5") (pintype "power_in"))
      (node (ref "U7") (pin "4") (pinfunction "VCONTROL_4") (pintype "power_in"))
      (node (ref "U7") (pin "5") (pinfunction "IN_5") (pintype "power_in"))
      (node (ref "U7") (pin "6") (pinfunction "IN_6") (pintype "power_in"))
      (node (ref "U8") (pin "1") (pinfunction "OUT_1") (pintype "power_in"))
      (node (ref "U8") (pin "2") (pinfunction "OUT_2") (pintype "power_in"))
      (node (ref "U8") (pin "7") (pinfunction "EP_7") (pintype "power_in"))
    )
    (net (code "3") (name "-2.5Analog") (class "Default")
      (node (ref "C46") (pin "2") (pinfunction "2_2") (pintype "passive"))
      (node (ref "C48") (pin "2") (pinfunction "2_2") (pintype "passive"))
      (node (ref "C49") (pin "2") (pinfunction "2_2") (pintype "passive"))
      (node (ref "C51") (pin "2") (pinfunction "2_2") (pintype "passive"))
      (node (ref "C60") (pin "1") (pinfunction "1_1") (pintype "passive"))
      (node (ref "U4") (pin "5") (pinfunction "V-_5") (pintype "power_in"))
      (node (ref "U5") (pin "4") (pinfunction "V-_4") (pintype "power_in"))
      (node (ref "U9") (pin "10") (pinfunction "OUT_10") (pintype "output"))
      (node (ref "U9") (pin "9") (pinfunction "OUT_9") (pintype "output"))
    )
    (net (code "4") (name "/1mV") (class "Default")
      (node (ref "C45") (pin "1") (pinfunction "1_1") (pintype "passive"))
      (node (ref "R17") (pin "2") (pinfunction "2_2") (pintype "passive"))
      (node (ref "R18") (pin "1") (pinfunction "A_1") (pintype "passive"))
      (node (ref "U6") (pin "3") (pinfunction "-IN_3") (pintype "input"))
    )
    (net (code "5") (name "/Anode") (class "Default")
      (node (ref "Anode") (pin "1") (pinfunction "1_1") (pintype "passive"))
      (node (ref "R12") (pin "1") (pinfunction "A_1") (pintype "passive"))
    )
    (net (code "6") (name "/Clear_charge") (class "Default")
      (node (ref "R13") (pin "2") (pinfunction "2_2") (pintype "passive"))
    )
    (net (code "7") (name "/DRef_2.048V") (class "Default")
      (node (ref "R17") (pin "1") (pinfunction "A_1") (pintype "passive"))
      (node (ref "U1") (pin "6") (pinfunction "REF_6") (pintype "output"))
    )
    (net (code "8") (name "/MaxPulseLevel") (class "Default")
      (node (ref "Pulse_M") (pin "1") (pinfunction "Signal_1") (pintype "input"))
      (node (ref "U5") (pin "6") (pinfunction "-IN_B_6") (pintype "input"))
      (node (ref "U5") (pin "7") (pinfunction "OUT_B_7") (pintype "output"))
    )
    (net (code "9") (name "/Negative_V") (class "Default")
      (node (ref "C59") (pin "1") (pinfunction "1_1") (pintype "passive"))
      (node (ref "R22") (pin "1") (pinfunction "A_1") (pintype "passive"))
      (node (ref "U9") (pin "1") (pinfunction "IN_1") (pintype "input"))
      (node (ref "U9") (pin "11") (pinfunction "IN_11") (pintype "input"))
      (node (ref "U9") (pin "2") (pinfunction "IN_2") (pintype "input"))
      (node (ref "U9") (pin "4") (pinfunction "IMONP_4") (pintype "output"))
      (node (ref "U9") (pin "6") (pinfunction "*SHDN_6") (pintype "output"))
    )
    (net (code "10") (name "/PeakVoltage") (class "Default")
      (node (ref "C44") (pin "1") (pinfunction "1_1") (pintype "passive"))
      (node (ref "D28") (pin "2") (pinfunction "K_2") (pintype "passive"))
      (node (ref "Q2") (pin "3") (pinfunction "D_3") (pintype "passive"))
      (node (ref "R15") (pin "1") (pinfunction "A_1") (pintype "passive"))
      (node (ref "U5") (pin "2") (pinfunction "-IN_A_2") (pintype "input"))
      (node (ref "U5") (pin "5") (pinfunction "+IN_B_5") (pintype "input"))
    )
    (net (code "11") (name "/PreampSigOUT") (class "Default")
      (node (ref "R14") (pin "1") (pinfunction "A_1") (pintype "passive"))
      (node (ref "R35") (pin "1") (pinfunction "A_1") (pintype "passive"))
      (node (ref "U4") (pin "6") (pinfunction "OUT_6") (pintype "output"))
      (node (ref "U5") (pin "3") (pinfunction "+IN_A_3") (pintype "input"))
      (node (ref "U6") (pin "2") (pinfunction "+IN_2") (pintype "input"))
    )
    (net (code "12") (name "/Pulse") (class "Default")
      (node (ref "R4") (pin "1") (pinfunction "A_1") (pintype "passive"))
    )
    (net (code "13") (name "/PulseSens") (class "Default")
      (node (ref "U6") (pin "8") (pinfunction "~{Q}_8") (pintype "output"))
    )
    (net (code "14") (name "/Pump") (class "Default")
      (node (ref "C5") (pin "2") (pinfunction "2_2") (pintype "passive"))
      (node (ref "T1") (pin "3") (pinfunction "3_3") (pintype "passive"))
    )
    (net (code "15") (name "/Up1") (class "Default")
      (node (ref "C31") (pin "1") (pinfunction "1_1") (pintype "passive"))
      (node (ref "C32") (pin "2") (pinfunction "2_2") (pintype "passive"))
      (node (ref "HV_Conn") (pin "1") (pinfunction "1_1") (pintype "passive"))
      (node (ref "R8") (pin "4") (pinfunction "4_4") (pintype "passive"))
    )
    (net (code "16") (name "/Up2") (class "Default")
      (node (ref "C32") (pin "1") (pinfunction "1_1") (pintype "passive"))
      (node (ref "C33") (pin "2") (pinfunction "2_2") (pintype "passive"))
      (node (ref "HV_Conn") (pin "2") (pinfunction "2_2") (pintype "passive"))
      (node (ref "R8") (pin "3") (pinfunction "3_3") (pintype "passive"))
    )
    (net (code "17") (name "/Up3") (class "Default")
      (node (ref "C33") (pin "1") (pinfunction "1_1") (pintype "passive"))
      (node (ref "C34") (pin "2") (pinfunction "2_2") (pintype "passive"))
      (node (ref "HV_Conn") (pin "3") (pinfunction "3_3") (pintype "passive"))
      (node (ref "R8") (pin "2") (pinfunction "2_2") (pintype "passive"))
    )
    (net (code "18") (name "/Up4") (class "Default")
      (node (ref "C34") (pin "1") (pinfunction "1_1") (pintype "passive"))
      (node (ref "C35") (pin "2") (pinfunction "2_2") (pintype "passive"))
      (node (ref "HV_Conn") (pin "4") (pinfunction "4_4") (pintype "passive"))
      (node (ref "R8") (pin "1") (pinfunction "1_1") (pintype "passive"))
    )
    (net (code "19") (name "/Up5") (class "Default")
      (node (ref "C35") (pin "1") (pinfunction "1_1") (pintype "passive"))
      (node (ref "C36") (pin "2") (pinfunction "2_2") (pintype "passive"))
      (node (ref "HV_Conn") (pin "5") (pinfunction "5_5") (pintype "passive"))
      (node (ref "R9") (pin "4") (pinfunction "4_4") (pintype "passive"))
    )
    (net (code "20") (name "/Up6") (class "Default")
      (node (ref "C36") (pin "1") (pinfunction "1_1") (pintype "passive"))
      (node (ref "C37") (pin "2") (pinfunction "2_2") (pintype "passive"))
      (node (ref "HV_Conn") (pin "6") (pinfunction "6_6") (pintype "passive"))
      (node (ref "R9") (pin "3") (pinfunction "3_3") (pintype "passive"))
    )
    (net (code "21") (name "/Up7") (class "Default")
      (node (ref "C37") (pin "1") (pinfunction "1_1") (pintype "passive"))
      (node (ref "C38") (pin "2") (pinfunction "2_2") (pintype "passive"))
      (node (ref "HV_Conn") (pin "7") (pinfunction "7_7") (pintype "passive"))
      (node (ref "R9") (pin "2") (pinfunction "2_2") (pintype "passive"))
    )
    (net (code "22") (name "/Up8") (class "Default")
      (node (ref "C38") (pin "1") (pinfunction "1_1") (pintype "passive"))
      (node (ref "C39") (pin "2") (pinfunction "2_2") (pintype "passive"))
      (node (ref "HV_Conn") (pin "8") (pinfunction "8_8") (pintype "passive"))
      (node (ref "R9") (pin "1") (pinfunction "1_1") (pintype "passive"))
    )
    (net (code "23") (name "/Up9") (class "Default")
      (node (ref "C39") (pin "1") (pinfunction "1_1") (pintype "passive"))
      (node (ref "C40") (pin "2") (pinfunction "2_2") (pintype "passive"))
      (node (ref "HV_Conn") (pin "9") (pinfunction "9_9") (pintype "passive"))
      (node (ref "R10") (pin "1") (pinfunction "1_1") (pintype "passive"))
    )
    (net (code "24") (name "/Up10") (class "Default")
      (node (ref "C40") (pin "1") (pinfunction "1_1") (pintype "passive"))
      (node (ref "C41") (pin "2") (pinfunction "2_2") (pintype "passive"))
      (node (ref "HV_Conn") (pin "10") (pinfunction "10_10") (pintype "passive"))
      (node (ref "R10") (pin "2") (pinfunction "2_2") (pintype "passive"))
    )
    (net (code "25") (name "/Up11") (class "Default")
      (node (ref "C41") (pin "1") (pinfunction "1_1") (pintype "passive"))
      (node (ref "C42") (pin "2") (pinfunction "2_2") (pintype "passive"))
      (node (ref "HV_Conn") (pin "11") (pinfunction "11_11") (pintype "passive"))
      (node (ref "R10") (pin "3") (pinfunction "3_3") (pintype "passive"))
    )
    (net (code "26") (name "/Up12") (class "Default")
      (node (ref "C42") (pin "1") (pinfunction "1_1") (pintype "passive"))
      (node (ref "HV_Conn") (pin "12") (pinfunction "12_12") (pintype "passive"))
      (node (ref "P2") (pin "1") (pinfunction "1_1") (pintype "passive"))
      (node (ref "R10") (pin "4") (pinfunction "4_4") (pintype "passive"))
    )
    (net (code "27") (name "/Vdigisenscan") (class "Default")
      (node (ref "U2") (pin "1") (pinfunction "OUT_1") (pintype "output"))
    )
    (net (code "28") (name "/VdigisetcanCLK") (class "Default")
      (node (ref "R6") (pin "5") (pinfunction "5_5") (pintype "passive"))
    )
    (net (code "29") (name "/VdigisetcanCS") (class "Default")
      (node (ref "R6") (pin "7") (pinfunction "7_7") (pintype "passive"))
    )
    (net (code "30") (name "/VdigisetcanDIN") (class "Default")
      (node (ref "R6") (pin "6") (pinfunction "6_6") (pintype "passive"))
    )
    (net (code "31") (name "/Vsens") (class "Default")
      (node (ref "R34") (pin "1") (pinfunction "A_1") (pintype "passive"))
      (node (ref "R7") (pin "2") (pinfunction "2_2") (pintype "passive"))
      (node (ref "U2") (pin "3") (pinfunction "+IN_3") (pintype "input"))
      (node (ref "U3") (pin "1") (pinfunction "OUT_1") (pintype "output"))
    )
    (net (code "32") (name "AGND") (class "Default")
      (node (ref "C30") (pin "2") (pinfunction "2_2") (pintype "passive"))
      (node (ref "C4") (pin "1") (pinfunction "1_1") (pintype "passive"))
      (node (ref "C43") (pin "2") (pinfunction "2_2") (pintype "passive"))
      (node (ref "C44") (pin "2") (pinfunction "2_2") (pintype "passive"))
      (node (ref "C45") (pin "2") (pinfunction "2_2") (pintype "passive"))
      (node (ref "C47") (pin "2") (pinfunction "2_2") (pintype "passive"))
      (node (ref "C50") (pin "2") (pinfunction "2_2") (pintype "passive"))
      (node (ref "C52") (pin "2") (pinfunction "2_2") (pintype "passive"))
      (node (ref "C53") (pin "2") (pinfunction "2_2") (pintype "passive"))
      (node (ref "ESD1") (pin "1") (pinfunction "1_1") (pintype "passive"))
      (node (ref "ESD2") (pin "1") (pinfunction "1_1") (pintype "passive"))
      (node (ref "ESD3") (pin "1") (pinfunction "1_1") (pintype "passive"))
      (node (ref "ESD4") (pin "1") (pinfunction "1_1") (pintype "passive"))
      (node (ref "ESD5") (pin "1") (pinfunction "1_1") (pintype "passive"))
      (node (ref "ESD6") (pin "1") (pinfunction "1_1") (pintype "passive"))
      (node (ref "ESD7") (pin "1") (pinfunction "1_1") (pintype "passive"))
      (node (ref "ESD8") (pin "1") (pinfunction "1_1") (pintype "passive"))
      (node (ref "Jumper") (pin "2") (pinfunction "2_2") (pintype "passive"))
      (node (ref "Jumper1") (pin "2") (pinfunction "2_2") (pintype "passive"))
      (node (ref "Jumper2") (pin "2") (pinfunction "2_2") (pintype "passive"))
      (node (ref "Pulse_M") (pin "2") (pinfunction "GND_2") (pintype "power_in"))
      (node (ref "Pulse_M") (pin "3") (pinfunction "GND_3") (pintype "power_in"))
      (node (ref "Pulse_M") (pin "4") (pinfunction "GND_4") (pintype "power_in"))
      (node (ref "Pulse_M") (pin "5") (pinfunction "GND_5") (pintype "power_in"))
      (node (ref "Q2") (pin "2") (pinfunction "S_2") (pintype "passive"))
      (node (ref "R15") (pin "2") (pinfunction "2_2") (pintype "passive"))
      (node (ref "R16") (pin "2") (pinfunction "2_2") (pintype "passive"))
      (node (ref "R18") (pin "2") (pinfunction "2_2") (pintype "passive"))
      (node (ref "R34") (pin "2") (pinfunction "2_2") (pintype "passive"))
      (node (ref "R35") (pin "2") (pinfunction "2_2") (pintype "passive"))
      (node (ref "U1") (pin "5") (pinfunction "GND_5") (pintype "power_in"))
      (node (ref "U2") (pin "2") (pinfunction "V-_2") (pintype "power_in"))
      (node (ref "U3") (pin "2") (pinfunction "V-_2") (pintype "power_in"))
      (node (ref "U3") (pin "3") (pinfunction "+IN_3") (pintype "input"))
      (node (ref "U4") (pin "1") (pinfunction "NC_1") (pintype "passive"))
      (node (ref "U4") (pin "3") (pinfunction "+IN_3") (pintype "input"))
      (node (ref "U6") (pin "4") (pinfunction "V-_4") (pintype "power_in"))
      (node (ref "U6") (pin "5") (pinfunction "LATCH_ENABLE_5") (pintype "input"))
      (node (ref "U6") (pin "6") (pinfunction "GND_6") (pintype "power_in"))
    )
    (net (code "33") (name "GND") (class "Default")
      (node (ref "C18") (pin "2") (pinfunction "2_2") (pintype "passive"))
      (node (ref "C2") (pin "2") (pinfunction "2_2") (pintype "passive"))
      (node (ref "C3") (pin "2") (pinfunction "2_2") (pintype "passive"))
      (node (ref "C31") (pin "2") (pinfunction "2_2") (pintype "passive"))
      (node (ref "C54") (pin "2") (pinfunction "2_2") (pintype "passive"))
      (node (ref "C55") (pin "2") (pinfunction "2_2") (pintype "passive"))
      (node (ref "C56") (pin "2") (pinfunction "2_2") (pintype "passive"))
      (node (ref "C57") (pin "2") (pinfunction "2_2") (pintype "passive"))
      (node (ref "C58") (pin "2") (pinfunction "2_2") (pintype "passive"))
      (node (ref "C59") (pin "2") (pinfunction "2_2") (pintype "passive"))
      (node (ref "C60") (pin "2") (pinfunction "2_2") (pintype "passive"))
      (node (ref "C61") (pin "2") (pinfunction "2_2") (pintype "passive"))
      (node (ref "C62") (pin "2") (pinfunction "2_2") (pintype "passive"))
      (node (ref "C64") (pin "2") (pinfunction "2_2") (pintype "passive"))
      (node (ref "D2") (pin "1") (pinfunction "A_1") (pintype "passive"))
      (node (ref "D3") (pin "2") (pinfunction "K_2") (pintype "passive"))
      (node (ref "Jumper") (pin "1") (pinfunction "A_1") (pintype "passive"))
      (node (ref "Jumper1") (pin "1") (pinfunction "A_1") (pintype "passive"))
      (node (ref "Jumper2") (pin "1") (pinfunction "A_1") (pintype "passive"))
      (node (ref "Q1") (pin "2") (pinfunction "S_2") (pintype "passive"))
      (node (ref "R19") (pin "2") (pinfunction "2_2") (pintype "passive"))
      (node (ref "R21") (pin "1") (pinfunction "A_1") (pintype "passive"))
      (node (ref "R23") (pin "1") (pinfunction "A_1") (pintype "passive"))
      (node (ref "R5") (pin "1") (pinfunction "A_1") (pintype "passive"))
      (node (ref "T1") (pin "2") (pinfunction "2_2") (pintype "passive"))
      (node (ref "U10") (pin "2") (pinfunction "GND_2") (pintype "power_in"))
      (node (ref "U9") (pin "5") (pinfunction "IMONN_5") (pintype "output"))
      (node (ref "U9") (pin "8") (pinfunction "GND_8") (pintype "power_in"))
    )
    (net (code "34") (name "Net-(D2-K)") (class "Default")
      (node (ref "C5") (pin "1") (pinfunction "1_1") (pintype "passive"))
      (node (ref "C6") (pin "2") (pinfunction "2_2") (pintype "passive"))
      (node (ref "D2") (pin "2") (pinfunction "K_2") (pintype "passive"))
    )
    (net (code "35") (name "Net-(D3-A)") (class "Default")
      (node (ref "C6") (pin "1") (pinfunction "1_1") (pintype "passive"))
      (node (ref "C7") (pin "2") (pinfunction "2_2") (pintype "passive"))
      (node (ref "D3") (pin "1") (pinfunction "A_1") (pintype "passive"))
      (node (ref "D4") (pin "2") (pinfunction "K_2") (pintype "passive"))
    )
    (net (code "36") (name "Net-(D4-A)") (class "Default")
      (node (ref "C18") (pin "1") (pinfunction "1_1") (pintype "passive"))
      (node (ref "C19") (pin "2") (pinfunction "2_2") (pintype "passive"))
      (node (ref "D4") (pin "1") (pinfunction "A_1") (pintype "passive"))
      (node (ref "D5") (pin "2") (pinfunction "K_2") (pintype "passive"))
      (node (ref "R8") (pin "8") (pinfunction "8_8") (pintype "passive"))
    )
    (net (code "37") (name "Net-(D5-A)") (class "Default")
      (node (ref "C7") (pin "1") (pinfunction "1_1") (pintype "passive"))
      (node (ref "C8") (pin "2") (pinfunction "2_2") (pintype "passive"))
      (node (ref "D5") (pin "1") (pinfunction "A_1") (pintype "passive"))
      (node (ref "D6") (pin "2") (pinfunction "K_2") (pintype "passive"))
    )
    (net (code "38") (name "Net-(D6-A)") (class "Default")
      (node (ref "C19") (pin "1") (pinfunction "1_1") (pintype "passive"))
      (node (ref "C20") (pin "2") (pinfunction "2_2") (pintype "passive"))
      (node (ref "D6") (pin "1") (pinfunction "A_1") (pintype "passive"))
      (node (ref "D7") (pin "2") (pinfunction "K_2") (pintype "passive"))
      (node (ref "R8") (pin "7") (pinfunction "7_7") (pintype "passive"))
    )
    (net (code "39") (name "Net-(D7-A)") (class "Default")
      (node (ref "C8") (pin "1") (pinfunction "1_1") (pintype "passive"))
      (node (ref "C9") (pin "2") (pinfunction "2_2") (pintype "passive"))
      (node (ref "D7") (pin "1") (pinfunction "A_1") (pintype "passive"))
      (node (ref "D8") (pin "2") (pinfunction "K_2") (pintype "passive"))
    )
    (net (code "40") (name "Net-(D8-A)") (class "Default")
      (node (ref "C20") (pin "1") (pinfunction "1_1") (pintype "passive"))
      (node (ref "C21") (pin "2") (pinfunction "2_2") (pintype "passive"))
      (node (ref "D8") (pin "1") (pinfunction "A_1") (pintype "passive"))
      (node (ref "D9") (pin "2") (pinfunction "K_2") (pintype "passive"))
      (node (ref "R8") (pin "6") (pinfunction "6_6") (pintype "passive"))
    )
    (net (code "41") (name "Net-(D10-A)") (class "Default")
      (node (ref "C21") (pin "1") (pinfunction "1_1") (pintype "passive"))
      (node (ref "C22") (pin "2") (pinfunction "2_2") (pintype "passive"))
      (node (ref "D10") (pin "1") (pinfunction "A_1") (pintype "passive"))
      (node (ref "D11") (pin "2") (pinfunction "K_2") (pintype "passive"))
      (node (ref "R8") (pin "5") (pinfunction "5_5") (pintype "passive"))
    )
    (net (code "42") (name "Net-(D10-K)") (class "Default")
      (node (ref "C10") (pin "2") (pinfunction "2_2") (pintype "passive"))
      (node (ref "C9") (pin "1") (pinfunction "1_1") (pintype "passive"))
      (node (ref "D10") (pin "2") (pinfunction "K_2") (pintype "passive"))
      (node (ref "D9") (pin "1") (pinfunction "A_1") (pintype "passive"))
    )
    (net (code "43") (name "Net-(D11-A)") (class "Default")
      (node (ref "C10") (pin "1") (pinfunction "1_1") (pintype "passive"))
      (node (ref "C11") (pin "2") (pinfunction "2_2") (pintype "passive"))
      (node (ref "D11") (pin "1") (pinfunction "A_1") (pintype "passive"))
      (node (ref "D12") (pin "2") (pinfunction "K_2") (pintype "passive"))
    )
    (net (code "44") (name "Net-(D12-A)") (class "Default")
      (node (ref "C22") (pin "1") (pinfunction "1_1") (pintype "passive"))
      (node (ref "C23") (pin "2") (pinfunction "2_2") (pintype "passive"))
      (node (ref "D12") (pin "1") (pinfunction "A_1") (pintype "passive"))
      (node (ref "D13") (pin "2") (pinfunction "K_2") (pintype "passive"))
      (node (ref "R9") (pin "8") (pinfunction "8_8") (pintype "passive"))
    )
    (net (code "45") (name "Net-(D13-A)") (class "Default")
      (node (ref "C11") (pin "1") (pinfunction "1_1") (pintype "passive"))
      (node (ref "C12") (pin "2") (pinfunction "2_2") (pintype "passive"))
      (node (ref "D13") (pin "1") (pinfunction "A_1") (pintype "passive"))
      (node (ref "D14") (pin "2") (pinfunction "K_2") (pintype "passive"))
    )
    (net (code "46") (name "Net-(D14-A)") (class "Default")
      (node (ref "C23") (pin "1") (pinfunction "1_1") (pintype "passive"))
      (node (ref "C24") (pin "2") (pinfunction "2_2") (pintype "passive"))
      (node (ref "D14") (pin "1") (pinfunction "A_1") (pintype "passive"))
      (node (ref "D15") (pin "2") (pinfunction "K_2") (pintype "passive"))
      (node (ref "R9") (pin "7") (pinfunction "7_7") (pintype "passive"))
    )
    (net (code "47") (name "Net-(D15-A)") (class "Default")
      (node (ref "C12") (pin "1") (pinfunction "1_1") (pintype "passive"))
      (node (ref "C13") (pin "2") (pinfunction "2_2") (pintype "passive"))
      (node (ref "D15") (pin "1") (pinfunction "A_1") (pintype "passive"))
      (node (ref "D16") (pin "2") (pinfunction "K_2") (pintype "passive"))
    )
    (net (code "48") (name "Net-(D16-A)") (class "Default")
      (node (ref "C24") (pin "1") (pinfunction "1_1") (pintype "passive"))
      (node (ref "C25") (pin "2") (pinfunction "2_2") (pintype "passive"))
      (node (ref "D16") (pin "1") (pinfunction "A_1") (pintype "passive"))
      (node (ref "D17") (pin "2") (pinfunction "K_2") (pintype "passive"))
      (node (ref "R9") (pin "6") (pinfunction "6_6") (pintype "passive"))
    )
    (net (code "49") (name "Net-(D17-A)") (class "Default")
      (node (ref "C13") (pin "1") (pinfunction "1_1") (pintype "passive"))
      (node (ref "C14") (pin "2") (pinfunction "2_2") (pintype "passive"))
      (node (ref "D17") (pin "1") (pinfunction "A_1") (pintype "passive"))
      (node (ref "D18") (pin "2") (pinfunction "K_2") (pintype "passive"))
    )
    (net (code "50") (name "Net-(D18-A)") (class "Default")
      (node (ref "C25") (pin "1") (pinfunction "1_1") (pintype "passive"))
      (node (ref "C26") (pin "2") (pinfunction "2_2") (pintype "passive"))
      (node (ref "D18") (pin "1") (pinfunction "A_1") (pintype "passive"))
      (node (ref "D19") (pin "2") (pinfunction "K_2") (pintype "passive"))
      (node (ref "R9") (pin "5") (pinfunction "5_5") (pintype "passive"))
    )
    (net (code "51") (name "Net-(D19-A)") (class "Default")
      (node (ref "C14") (pin "1") (pinfunction "1_1") (pintype "passive"))
      (node (ref "C15") (pin "2") (pinfunction "2_2") (pintype "passive"))
      (node (ref "D19") (pin "1") (pinfunction "A_1") (pintype "passive"))
      (node (ref "D20") (pin "2") (pinfunction "K_2") (pintype "passive"))
    )
    (net (code "52") (name "Net-(D20-A)") (class "Default")
      (node (ref "C26") (pin "1") (pinfunction "1_1") (pintype "passive"))
      (node (ref "C27") (pin "2") (pinfunction "2_2") (pintype "passive"))
      (node (ref "D20") (pin "1") (pinfunction "A_1") (pintype "passive"))
      (node (ref "D21") (pin "2") (pinfunction "K_2") (pintype "passive"))
      (node (ref "R10") (pin "5") (pinfunction "5_5") (pintype "passive"))
    )
    (net (code "53") (name "Net-(D21-A)") (class "Default")
      (node (ref "C15") (pin "1") (pinfunction "1_1") (pintype "passive"))
      (node (ref "C16") (pin "2") (pinfunction "2_2") (pintype "passive"))
      (node (ref "D21") (pin "1") (pinfunction "A_1") (pintype "passive"))
      (node (ref "D22") (pin "2") (pinfunction "K_2") (pintype "passive"))
    )
    (net (code "54") (name "Net-(D22-A)") (class "Default")
      (node (ref "C27") (pin "1") (pinfunction "1_1") (pintype "passive"))
      (node (ref "C28") (pin "2") (pinfunction "2_2") (pintype "passive"))
      (node (ref "D22") (pin "1") (pinfunction "A_1") (pintype "passive"))
      (node (ref "D23") (pin "2") (pinfunction "K_2") (pintype "passive"))
      (node (ref "R10") (pin "6") (pinfunction "6_6") (pintype "passive"))
    )
    (net (code "55") (name "Net-(D23-A)") (class "Default")
      (node (ref "C16") (pin "1") (pinfunction "1_1") (pintype "passive"))
      (node (ref "C17") (pin "2") (pinfunction "2_2") (pintype "passive"))
      (node (ref "D23") (pin "1") (pinfunction "A_1") (pintype "passive"))
      (node (ref "D24") (pin "2") (pinfunction "K_2") (pintype "passive"))
    )
    (net (code "56") (name "Net-(D24-A)") (class "Default")
      (node (ref "C28") (pin "1") (pinfunction "1_1") (pintype "passive"))
      (node (ref "C29") (pin "2") (pinfunction "2_2") (pintype "passive"))
      (node (ref "D24") (pin "1") (pinfunction "A_1") (pintype "passive"))
      (node (ref "D25") (pin "2") (pinfunction "K_2") (pintype "passive"))
      (node (ref "R10") (pin "7") (pinfunction "7_7") (pintype "passive"))
    )
    (net (code "57") (name "Net-(D25-A)") (class "Default")
      (node (ref "C17") (pin "1") (pinfunction "1_1") (pintype "passive"))
      (node (ref "D25") (pin "1") (pinfunction "A_1") (pintype "passive"))
      (node (ref "D26") (pin "2") (pinfunction "K_2") (pintype "passive"))
    )
    (net (code "58") (name "Net-(D26-A)") (class "Default")
      (node (ref "C29") (pin "1") (pinfunction "1_1") (pintype "passive"))
      (node (ref "D26") (pin "1") (pinfunction "A_1") (pintype "passive"))
      (node (ref "P2") (pin "3") (pinfunction "3_3") (pintype "passive"))
      (node (ref "R10") (pin "8") (pinfunction "8_8") (pintype "passive"))
    )
    (net (code "59") (name "Net-(D28-A)") (class "Default")
      (node (ref "D28") (pin "1") (pinfunction "A_1") (pintype "passive"))
      (node (ref "R11") (pin "2") (pinfunction "2_2") (pintype "passive"))
    )
    (net (code "60") (name "Net-(P2-Pad2)") (class "Default")
      (node (ref "P2") (pin "2") (pinfunction "2_2") (pintype "passive"))
      (node (ref "R7") (pin "1") (pinfunction "1_1") (pintype "passive"))
    )
    (net (code "61") (name "Net-(Q1-D)") (class "Default")
      (node (ref "D1") (pin "K") (pinfunction "K_K") (pintype "passive"))
      (node (ref "Q1") (pin "3") (pinfunction "D_3") (pintype "passive"))
      (node (ref "T1") (pin "4") (pintype "passive"))
    )
    (net (code "62") (name "Net-(Q1-G)") (class "Default")
      (node (ref "Q1") (pin "1") (pinfunction "G_1") (pintype "passive"))
      (node (ref "R4") (pin "2") (pinfunction "2_2") (pintype "passive"))
      (node (ref "R5") (pin "2") (pinfunction "2_2") (pintype "passive"))
    )
    (net (code "63") (name "Net-(Q2-G)") (class "Default")
      (node (ref "Q2") (pin "1") (pinfunction "G_1") (pintype "passive"))
      (node (ref "R13") (pin "1") (pinfunction "A_1") (pintype "passive"))
      (node (ref "R16") (pin "1") (pinfunction "A_1") (pintype "passive"))
    )
    (net (code "64") (name "Net-(R1-A)") (class "Default")
      (node (ref "C1") (pin "1") (pinfunction "1_1") (pintype "passive"))
      (node (ref "D1") (pin "A") (pinfunction "A_A") (pintype "passive"))
      (node (ref "R1") (pin "1") (pinfunction "A_1") (pintype "passive"))
    )
    (net (code "65") (name "Net-(R2-A)") (class "Default")
      (node (ref "C1") (pin "2") (pinfunction "2_2") (pintype "passive"))
      (node (ref "R1") (pin "2") (pinfunction "2_2") (pintype "passive"))
      (node (ref "R2") (pin "1") (pinfunction "A_1") (pintype "passive"))
    )
    (net (code "66") (name "Net-(R3-A)") (class "Default")
      (node (ref "C2") (pin "1") (pinfunction "1_1") (pintype "passive"))
      (node (ref "R2") (pin "2") (pinfunction "2_2") (pintype "passive"))
      (node (ref "R3") (pin "1") (pinfunction "A_1") (pintype "passive"))
      (node (ref "T1") (pin "1") (pinfunction "1_1") (pintype "passive"))
    )
    (net (code "67") (name "Net-(R11-A)") (class "Default")
      (node (ref "R11") (pin "1") (pinfunction "A_1") (pintype "passive"))
      (node (ref "U5") (pin "1") (pinfunction "OUT_A_1") (pintype "output"))
    )
    (net (code "68") (name "Net-(R19-A)") (class "Default")
      (node (ref "C55") (pin "1") (pinfunction "1_1") (pintype "passive"))
      (node (ref "R19") (pin "1") (pinfunction "A_1") (pintype "passive"))
      (node (ref "U7") (pin "3") (pinfunction "SET_3") (pintype "input"))
    )
    (net (code "69") (name "Net-(R20-A)") (class "Default")
      (node (ref "R20") (pin "1") (pinfunction "A_1") (pintype "passive"))
      (node (ref "R21") (pin "2") (pinfunction "2_2") (pintype "passive"))
    )
    (net (code "70") (name "Net-(U1-*CS{slash}LD)") (class "Default")
      (node (ref "R6") (pin "3") (pinfunction "3_3") (pintype "passive"))
      (node (ref "U1") (pin "3") (pinfunction "*CS/LD_3") (pintype "bidirectional"))
    )
    (net (code "71") (name "Net-(U1-CLK)") (class "Default")
      (node (ref "R6") (pin "1") (pinfunction "1_1") (pintype "passive"))
      (node (ref "U1") (pin "1") (pinfunction "CLK_1") (pintype "input"))
    )
    (net (code "72") (name "Net-(U1-DIN)") (class "Default")
      (node (ref "R6") (pin "2") (pinfunction "2_2") (pintype "passive"))
      (node (ref "U1") (pin "2") (pinfunction "DIN_2") (pintype "input"))
    )
    (net (code "73") (name "Net-(U1-VOUT)") (class "Default")
      (node (ref "C4") (pin "2") (pinfunction "2_2") (pintype "passive"))
      (node (ref "U1") (pin "7") (pinfunction "VOUT_7") (pintype "output"))
      (node (ref "U2") (pin "4") (pinfunction "-IN_4") (pintype "input"))
    )
    (net (code "74") (name "Net-(U3--IN)") (class "Default")
      (node (ref "R7") (pin "3") (pinfunction "3_3") (pintype "passive"))
      (node (ref "U3") (pin "4") (pinfunction "-IN_4") (pintype "input"))
    )
    (net (code "75") (name "Net-(U4--IN)") (class "Default")
      (node (ref "R12") (pin "2") (pinfunction "2_2") (pintype "passive"))
      (node (ref "R14") (pin "2") (pinfunction "2_2") (pintype "passive"))
      (node (ref "U4") (pin "2") (pinfunction "-IN_2") (pintype "input"))
    )
    (net (code "76") (name "Net-(U8-SET)") (class "Default")
      (node (ref "C58") (pin "1") (pinfunction "1_1") (pintype "passive"))
      (node (ref "R20") (pin "2") (pinfunction "2_2") (pintype "passive"))
      (node (ref "U8") (pin "3") (pinfunction "SET_3") (pintype "input"))
    )
    (net (code "77") (name "Net-(U9-ILIM)") (class "Default")
      (node (ref "R22") (pin "2") (pinfunction "2_2") (pintype "passive"))
      (node (ref "U9") (pin "3") (pinfunction "ILIM_3") (pintype "passive"))
    )
    (net (code "78") (name "Net-(U9-SET)") (class "Default")
      (node (ref "C61") (pin "1") (pinfunction "1_1") (pintype "passive"))
      (node (ref "R23") (pin "2") (pinfunction "2_2") (pintype "passive"))
      (node (ref "U9") (pin "7") (pinfunction "SET_7") (pintype "input"))
    )
    (net (code "79") (name "Net-(U10-BYP)") (class "Default")
      (node (ref "C63") (pin "1") (pinfunction "1_1") (pintype "passive"))
      (node (ref "U10") (pin "4") (pinfunction "BYP_4") (pintype "passive"))
    )
    (net (code "80") (name "Net-(U10-OUT)") (class "Default")
      (node (ref "C63") (pin "2") (pinfunction "2_2") (pintype "passive"))
      (node (ref "C64") (pin "1") (pinfunction "1_1") (pintype "passive"))
      (node (ref "R3") (pin "2") (pinfunction "2_2") (pintype "passive"))
      (node (ref "U10") (pin "5") (pinfunction "OUT_5") (pintype "power_in"))
    )
    (net (code "81") (name "V_IN") (class "Default")
      (node (ref "C56") (pin "1") (pinfunction "1_1") (pintype "passive"))
      (node (ref "C62") (pin "1") (pinfunction "1_1") (pintype "passive"))
      (node (ref "U10") (pin "1") (pinfunction "IN_1") (pintype "power_in"))
      (node (ref "U10") (pin "3") (pinfunction "~{SHDN}_3") (pintype "input"))
      (node (ref "U8") (pin "4") (pinfunction "VCONTROL_4") (pintype "power_in"))
      (node (ref "U8") (pin "5") (pinfunction "IN_5") (pintype "power_in"))
      (node (ref "U8") (pin "6") (pinfunction "IN_6") (pintype "power_in"))
    )
    (net (code "82") (name "unconnected-(R6-Pad4)") (class "Default")
      (node (ref "R6") (pin "4") (pinfunction "4_4") (pintype "passive"))
    )
    (net (code "83") (name "unconnected-(R6-Pad8)") (class "Default")
      (node (ref "R6") (pin "8") (pinfunction "8_8") (pintype "passive"))
    )
    (net (code "84") (name "unconnected-(U1-DOUT-Pad4)") (class "Default")
      (node (ref "U1") (pin "4") (pinfunction "DOUT_4") (pintype "output"))
    )
    (net (code "85") (name "unconnected-(U4-*SHDN-Pad8)") (class "Default")
      (node (ref "U4") (pin "8") (pinfunction "*SHDN_8") (pintype "passive"))
    )
    (net (code "86") (name "unconnected-(U4-NC-Pad4)") (class "Default")
      (node (ref "U4") (pin "4") (pinfunction "NC_4") (pintype "passive"))
    )
    (net (code "87") (name "unconnected-(U6-Q-Pad7)") (class "Default")
      (node (ref "U6") (pin "7") (pinfunction "Q_7") (pintype "output"))
    )
  )
)
